# Front_left_lamp_v3.net
KiCad netlist of a schematic drawn in EAGLE
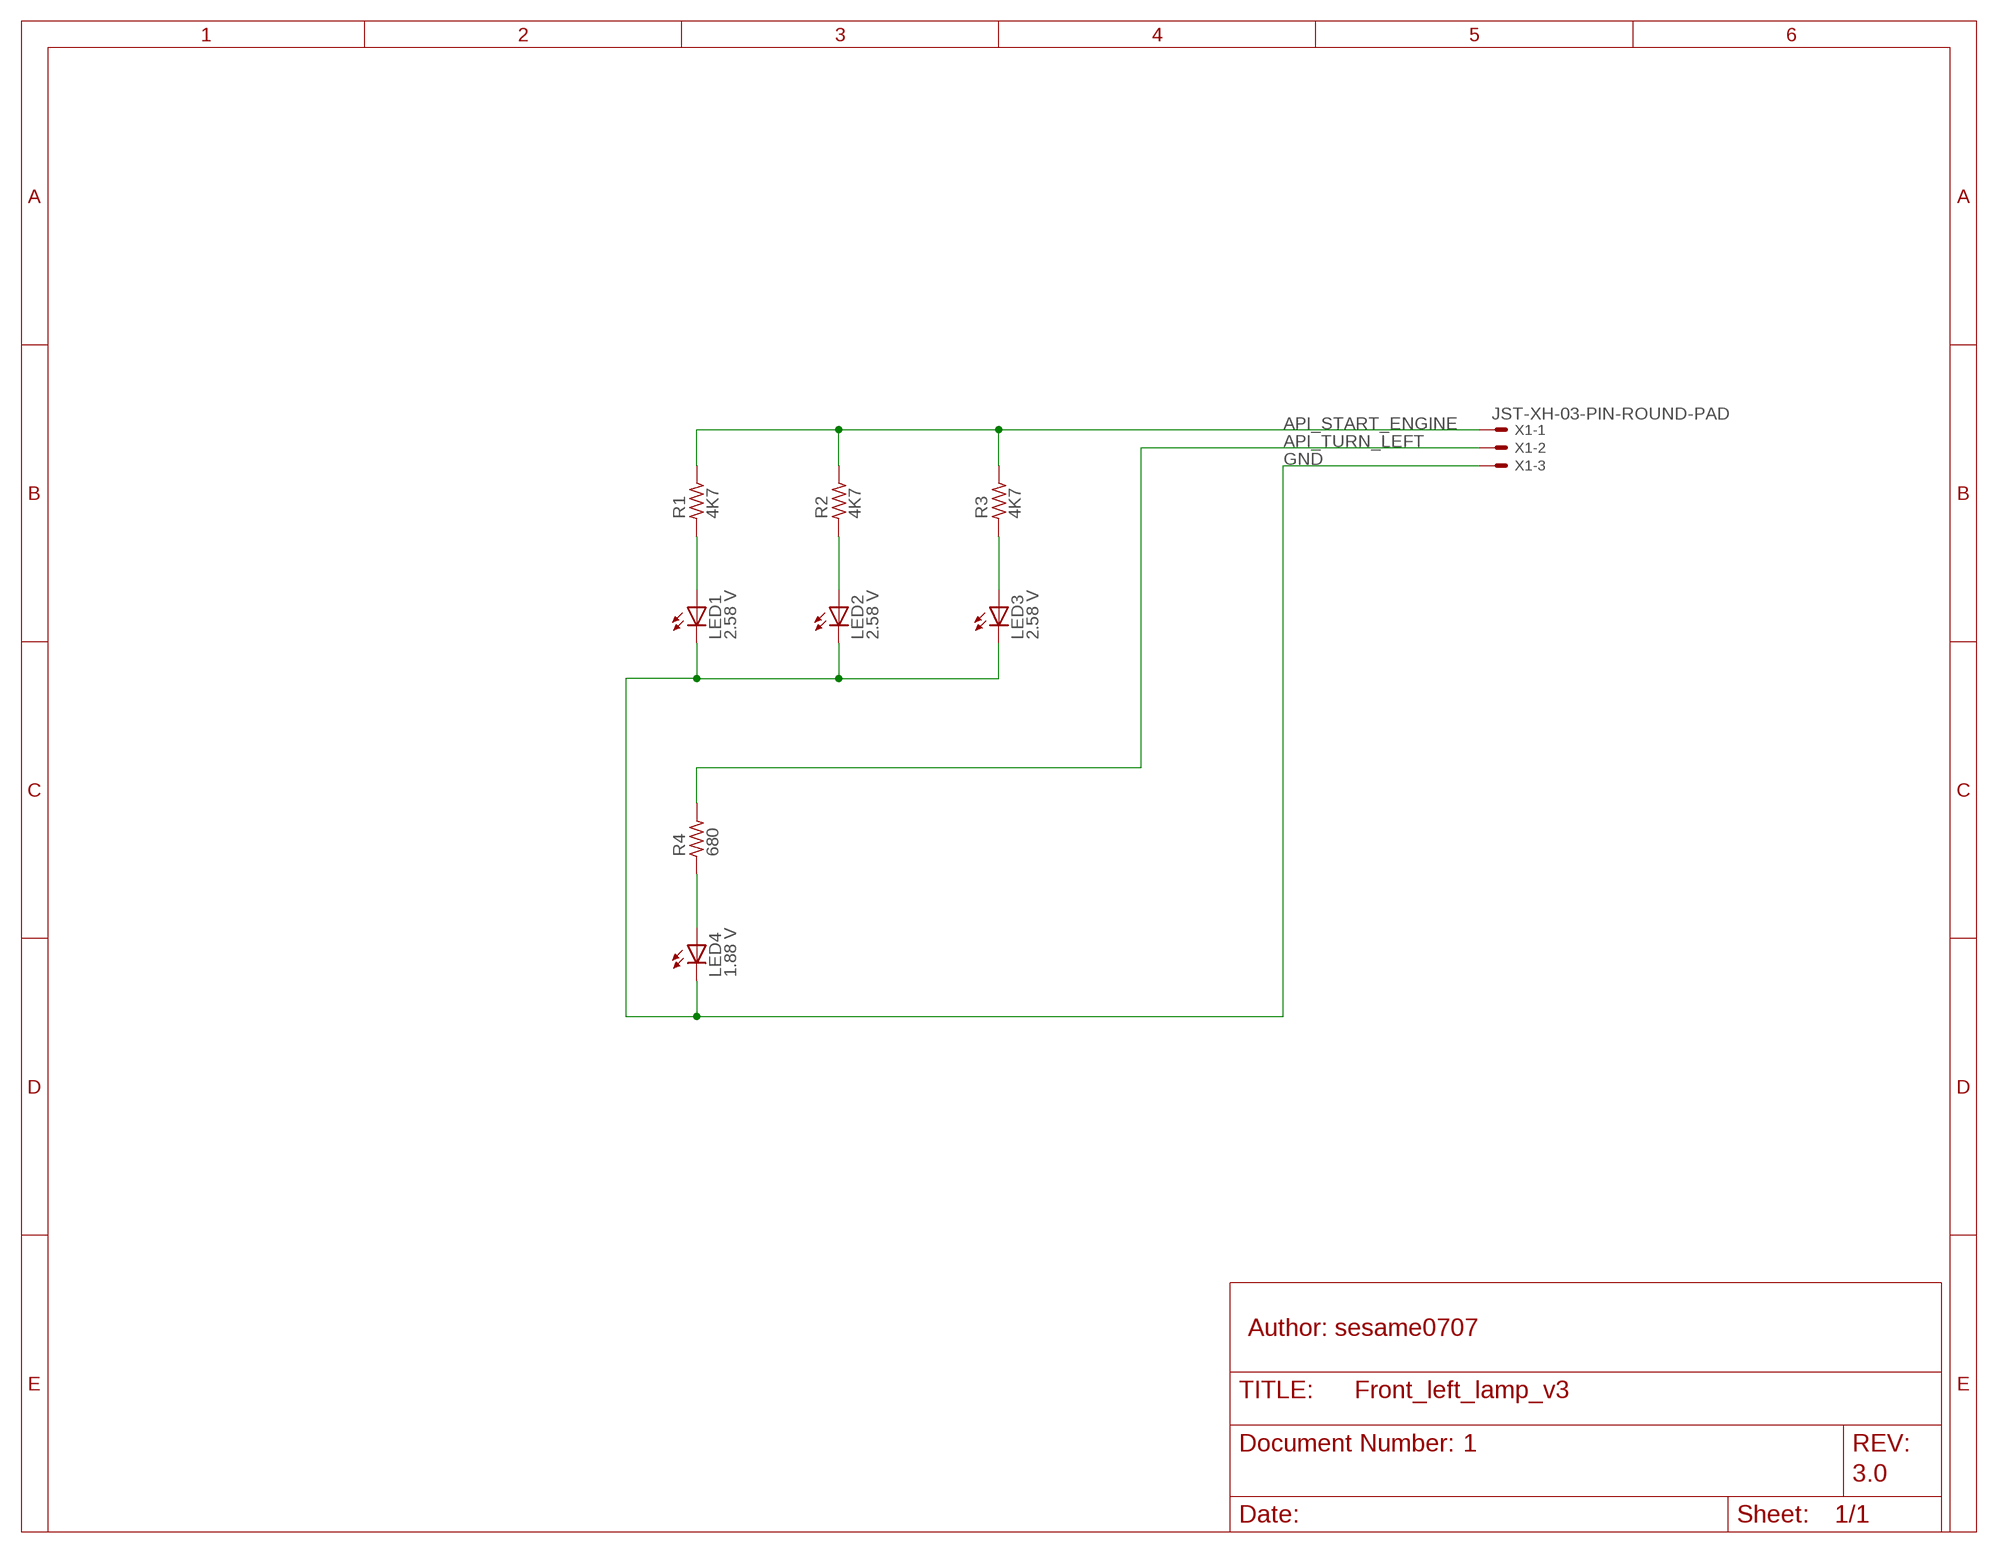
[diagram p0: schematic, sheet 1]

(export (version "E")
  (design (tool "Eeschema 10.0.6"))
  (components
    (comp (ref "LED1")
      (value "2.58 V")
      (footprint "eagle-import:LED5MM")
      (libsource (lib "eagle-import") (part "LED5MM"))
    )
    (comp (ref "LED2")
      (value "2.58 V")
      (footprint "eagle-import:LED5MM")
      (libsource (lib "eagle-import") (part "LED5MM"))
    )
    (comp (ref "LED3")
      (value "2.58 V")
      (footprint "eagle-import:LED5MM")
      (libsource (lib "eagle-import") (part "LED5MM"))
    )
    (comp (ref "LED4")
      (value "1.88 V")
      (footprint "eagle-import:LED5MM")
      (libsource (lib "eagle-import") (part "LED5MM"))
    )
    (comp (ref "R1")
      (value "4K7")
      (footprint "eagle-import:R0805")
      (libsource (lib "eagle-import") (part "R_0805"))
    )
    (comp (ref "R2")
      (value "4K7")
      (footprint "eagle-import:R0805")
      (libsource (lib "eagle-import") (part "R_0805"))
    )
    (comp (ref "R3")
      (value "4K7")
      (footprint "eagle-import:R0805")
      (libsource (lib "eagle-import") (part "R_0805"))
    )
    (comp (ref "R4")
      (value "680")
      (footprint "eagle-import:R0805")
      (libsource (lib "eagle-import") (part "R_0805"))
    )
    (comp (ref "X1")
      (value "JST-XH-03-PIN-ROUND-PAD")
      (footprint "eagle-import:JST-XH-03-PACKAGE-ROUND-PAD")
      (libsource (lib "eagle-import") (part "JST-XH-03-PIN-ROUND-PAD"))
    )
  )
  (nets
    (net (code "1") (name "/API_START_ENGINE") (class "Default")
      (node (ref "R1") (pin "2") (pinfunction "2_2") (pintype "passive"))
      (node (ref "R2") (pin "2") (pinfunction "2_2") (pintype "passive"))
      (node (ref "R3") (pin "2") (pinfunction "2_2") (pintype "passive"))
      (node (ref "X1") (pin "1") (pinfunction "S_1") (pintype "passive"))
    )
    (net (code "2") (name "/API_TURN_LEFT") (class "Default")
      (node (ref "R4") (pin "2") (pinfunction "2_2") (pintype "passive"))
      (node (ref "X1") (pin "2") (pinfunction "S_2") (pintype "passive"))
    )
    (net (code "3") (name "/GND") (class "Default")
      (node (ref "LED1") (pin "K") (pinfunction "C_K") (pintype "passive"))
      (node (ref "LED2") (pin "K") (pinfunction "C_K") (pintype "passive"))
      (node (ref "LED3") (pin "K") (pinfunction "C_K") (pintype "passive"))
      (node (ref "LED4") (pin "K") (pinfunction "C_K") (pintype "passive"))
      (node (ref "X1") (pin "3") (pinfunction "S_3") (pintype "passive"))
    )
    (net (code "4") (name "Net-(LED1-PadA)") (class "Default")
      (node (ref "LED1") (pin "A") (pinfunction "A_A") (pintype "passive"))
      (node (ref "R1") (pin "1") (pinfunction "1_1") (pintype "passive"))
    )
    (net (code "5") (name "Net-(LED2-PadA)") (class "Default")
      (node (ref "LED2") (pin "A") (pinfunction "A_A") (pintype "passive"))
      (node (ref "R2") (pin "1") (pinfunction "1_1") (pintype "passive"))
    )
    (net (code "6") (name "Net-(LED3-PadA)") (class "Default")
      (node (ref "LED3") (pin "A") (pinfunction "A_A") (pintype "passive"))
      (node (ref "R3") (pin "1") (pinfunction "1_1") (pintype "passive"))
    )
    (net (code "7") (name "Net-(LED4-PadA)") (class "Default")
      (node (ref "LED4") (pin "A") (pinfunction "A_A") (pintype "passive"))
      (node (ref "R4") (pin "1") (pinfunction "1_1") (pintype "passive"))
    )
  )
)
